# PV_MCU_IO.net
KiCad netlist of a schematic drawn in Altium Designer
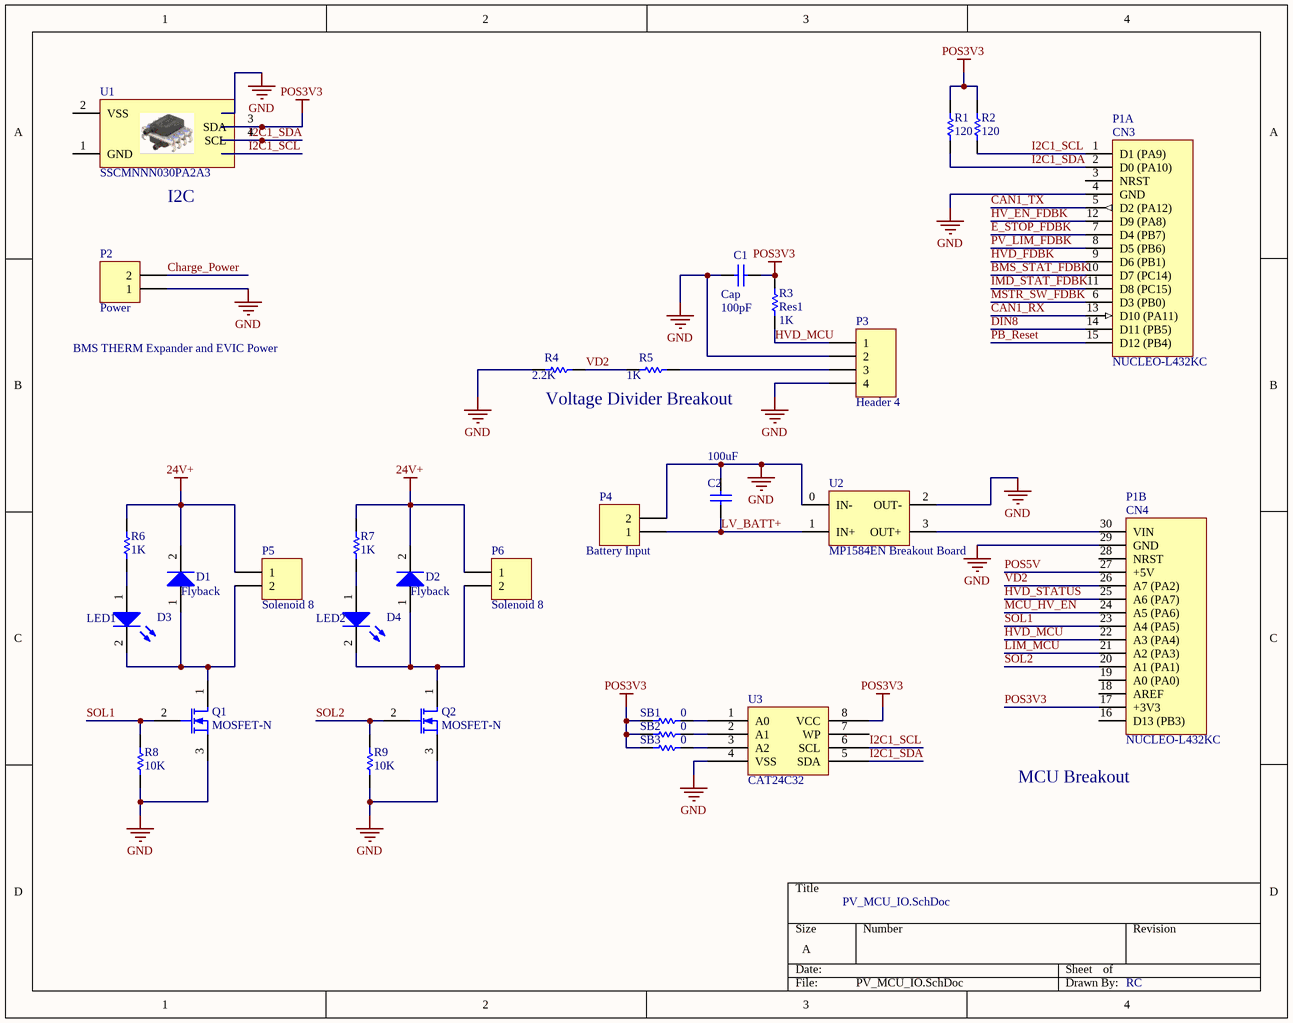
[diagram p0: PV_MCU_IO.SchDoc]

(export (version "E")
  (design (tool "Eeschema 10.0.6"))
  (components
    (comp (ref "C1")
      (value "Cap")
      (footprint "1206")
      (description "Capacitor")
      (fields (field (name "ALTIUM_VALUE") "100pF") (field (name "PUBLISHER") "Altium Limited"))
      (libsource (lib "Miscellaneous Devices") (part "Cap"))
    )
    (comp (ref "C2")
      (value "100uF")
      (footprint "CAPR5-4X5")
      (description "Capacitor")
      (fields (field (name "Comment") "Cap") (field (name "PUBLISHER") "Altium Limited"))
      (libsource (lib "Miscellaneous Devices") (part "Cap"))
    )
    (comp (ref "D1")
      (value "Flyback")
      (footprint "1N4007")
      (description "Default Diode")
      (fields (field (name "PUBLISHER") "Altium Limited"))
      (libsource (lib "Miscellaneous Devices") (part "Diode"))
    )
    (comp (ref "D2")
      (value "Flyback")
      (footprint "1N4007")
      (description "Default Diode")
      (fields (field (name "PUBLISHER") "Altium Limited"))
      (libsource (lib "Miscellaneous Devices") (part "Diode"))
    )
    (comp (ref "D3")
      (value "LED1")
      (footprint "1206 LED")
      (description "Typical RED, GREEN, YELLOW, AMBER GaAs LED")
      (fields (field (name "PUBLISHER") "Altium Limited"))
      (libsource (lib "Miscellaneous Devices") (part "LED2"))
    )
    (comp (ref "D4")
      (value "LED2")
      (footprint "1206 LED")
      (description "Typical RED, GREEN, YELLOW, AMBER GaAs LED")
      (fields (field (name "PUBLISHER") "Altium Limited"))
      (libsource (lib "Miscellaneous Devices") (part "LED2"))
    )
    (comp (ref "P1")
      (value "NUCLEO-L432KC")
      (footprint "NUCLEO-32")
      (description "STM32L432KC Development Board")
      (libsource (lib "ic") (part "NUCLEO-L432KC"))
    )
    (comp (ref "P2")
      (value "Power")
      (footprint "2POS TERM BLOCK")
      (description "Header, 2-Pin")
      (fields (field (name "PUBLISHER") "Altium Limited"))
      (libsource (lib "Miscellaneous Connectors") (part "Header 2"))
    )
    (comp (ref "P3")
      (value "Header 4")
      (footprint "4POS TERM BLOCK")
      (description "Header, 4-Pin")
      (fields (field (name "PUBLISHER") "Altium Limited"))
      (libsource (lib "Miscellaneous Connectors") (part "Header 4"))
    )
    (comp (ref "P4")
      (value "Battery Input")
      (footprint "2POS TERM BLOCK")
      (description "Header, 2-Pin")
      (fields (field (name "PUBLISHER") "Altium Limited"))
      (libsource (lib "Miscellaneous Connectors") (part "Header 2"))
    )
    (comp (ref "P5")
      (value "Solenoid 8")
      (footprint "2POS TERM BLOCK")
      (description "Header, 2-Pin")
      (fields (field (name "PUBLISHER") "Altium Limited"))
      (libsource (lib "") (part "Header 2_1"))
    )
    (comp (ref "P6")
      (value "Solenoid 8")
      (footprint "2POS TERM BLOCK")
      (description "Header, 2-Pin")
      (fields (field (name "PUBLISHER") "Altium Limited"))
      (libsource (lib "") (part "Header 2_1"))
    )
    (comp (ref "Q1")
      (value "MOSFET-N")
      (footprint "SOT-23-3")
      (description "N-Channel MOSFET")
      (fields (field (name "PUBLISHER") "Altium Limited"))
      (libsource (lib "Miscellaneous Devices") (part "MOSFET-N"))
    )
    (comp (ref "Q2")
      (value "MOSFET-N")
      (footprint "SOT-23-3")
      (description "N-Channel MOSFET")
      (fields (field (name "PUBLISHER") "Altium Limited"))
      (libsource (lib "Miscellaneous Devices") (part "MOSFET-N"))
    )
    (comp (ref "R1")
      (value "120")
      (footprint "1206")
      (description "Resistor")
      (fields (field (name "Comment") "Res1") (field (name "PUBLISHER") "Altium Limited"))
      (libsource (lib "Miscellaneous Devices") (part "Res1"))
    )
    (comp (ref "R2")
      (value "120")
      (footprint "1206")
      (description "Resistor")
      (fields (field (name "Comment") "Res1") (field (name "PUBLISHER") "Altium Limited"))
      (libsource (lib "Miscellaneous Devices") (part "Res1"))
    )
    (comp (ref "R3")
      (value "Res1")
      (footprint "1206")
      (description "Resistor")
      (fields (field (name "ALTIUM_VALUE") "1K") (field (name "PUBLISHER") "Altium Limited"))
      (libsource (lib "Miscellaneous Devices") (part "Res1"))
    )
    (comp (ref "R4")
      (value "2.2K")
      (footprint "1206")
      (description "Resistor")
      (fields (field (name "Comment") "Res1") (field (name "PUBLISHER") "Altium Limited"))
      (libsource (lib "Miscellaneous Devices") (part "Res1"))
    )
    (comp (ref "R5")
      (value "1K")
      (footprint "1206")
      (description "Resistor")
      (fields (field (name "Comment") "Res1") (field (name "PUBLISHER") "Altium Limited"))
      (libsource (lib "Miscellaneous Devices") (part "Res1"))
    )
    (comp (ref "R6")
      (value "1K")
      (footprint "1206")
      (description "Resistor")
      (fields (field (name "Comment") "Res1") (field (name "PUBLISHER") "Altium Limited"))
      (libsource (lib "Miscellaneous Devices") (part "Res1"))
    )
    (comp (ref "R7")
      (value "1K")
      (footprint "1206")
      (description "Resistor")
      (fields (field (name "Comment") "Res1") (field (name "PUBLISHER") "Altium Limited"))
      (libsource (lib "Miscellaneous Devices") (part "Res1"))
    )
    (comp (ref "R8")
      (value "10K")
      (footprint "1206")
      (description "Resistor")
      (fields (field (name "Comment") "Res1") (field (name "PUBLISHER") "Altium Limited"))
      (libsource (lib "Miscellaneous Devices") (part "Res1"))
    )
    (comp (ref "R9")
      (value "10K")
      (footprint "1206")
      (description "Resistor")
      (fields (field (name "Comment") "Res1") (field (name "PUBLISHER") "Altium Limited"))
      (libsource (lib "Miscellaneous Devices") (part "Res1"))
    )
    (comp (ref "SB1")
      (value "0")
      (footprint "6-0805_M")
      (description "Resistor")
      (fields (field (name "Comment") "Res1") (field (name "PUBLISHER") "Altium Limited"))
      (libsource (lib "Miscellaneous Devices") (part "Res1"))
    )
    (comp (ref "SB2")
      (value "0")
      (footprint "6-0805_M")
      (description "Resistor")
      (fields (field (name "Comment") "Res1") (field (name "PUBLISHER") "Altium Limited"))
      (libsource (lib "Miscellaneous Devices") (part "Res1"))
    )
    (comp (ref "SB3")
      (value "0")
      (footprint "6-0805_M")
      (description "Resistor")
      (fields (field (name "Comment") "Res1") (field (name "PUBLISHER") "Altium Limited"))
      (libsource (lib "Miscellaneous Devices") (part "Res1"))
    )
    (comp (ref "U1")
      (value "SSCMNNN030PA2A3")
      (footprint "8-SMT")
      (description "Honeywell Digital Pressure Sensor")
      (libsource (lib "ic") (part "SSCMNNN030PA2A3"))
    )
    (comp (ref "U2")
      (value "MP1584EN Breakout Board")
      (footprint "MP1584EN Breakout")
      (description "Buck Converter")
      (libsource (lib "ic") (part "MP1584EN Breakout Board"))
    )
    (comp (ref "U3")
      (value "CAT24C32")
      (footprint "SO8_N")
      (description "I2C EEPROM")
      (libsource (lib "ic") (part "CAT24C32"))
    )
  )
  (nets
    (net (code "1") (name "/BMS_STAT_FDBK") (class "Default")
      (node (ref "P1") (pin "10") (pinfunction "D7_(PC14)_10") (pintype "passive"))
    )
    (net (code "2") (name "/CAN1_RX") (class "Default")
      (node (ref "P1") (pin "13") (pinfunction "D10_(PA11)_13") (pintype "input"))
    )
    (net (code "3") (name "/CAN1_TX") (class "Default")
      (node (ref "P1") (pin "5") (pinfunction "D2_(PA12)_5") (pintype "output"))
    )
    (net (code "4") (name "/Charge_Power") (class "Default")
      (node (ref "P2") (pin "2") (pinfunction "2_2") (pintype "passive"))
    )
    (net (code "5") (name "/DIN8") (class "Default")
      (node (ref "P1") (pin "14") (pinfunction "D11_(PB5)_14") (pintype "passive"))
    )
    (net (code "6") (name "/E_STOP_FDBK") (class "Default")
      (node (ref "P1") (pin "7") (pinfunction "D4_(PB7)_7") (pintype "passive"))
    )
    (net (code "7") (name "/HVD_FDBK") (class "Default")
      (node (ref "P1") (pin "9") (pinfunction "D6_(PB1)_9") (pintype "passive"))
    )
    (net (code "8") (name "/HVD_MCU") (class "Default")
      (node (ref "P1") (pin "22") (pinfunction "A3_(PA4)_22") (pintype "passive"))
      (node (ref "P3") (pin "1") (pinfunction "1_1") (pintype "passive"))
      (node (ref "R3") (pin "1") (pinfunction "1_1") (pintype "passive"))
    )
    (net (code "9") (name "/HVD_STATUS") (class "Default")
      (node (ref "P1") (pin "25") (pinfunction "A6_(PA7)_25") (pintype "passive"))
    )
    (net (code "10") (name "/HV_EN_FDBK") (class "Default")
      (node (ref "P1") (pin "12") (pinfunction "D9_(PA8)_12") (pintype "passive"))
    )
    (net (code "11") (name "/I2C1_SCL") (class "Default")
      (node (ref "P1") (pin "1") (pinfunction "D1_(PA9)_1") (pintype "passive"))
      (node (ref "R2") (pin "1") (pinfunction "1_1") (pintype "passive"))
      (node (ref "U3") (pin "6") (pinfunction "SCL_6") (pintype "passive"))
    )
    (net (code "12") (name "/I2C1_SDA") (class "Default")
      (node (ref "P1") (pin "2") (pinfunction "D0_(PA10)_2") (pintype "passive"))
      (node (ref "R1") (pin "1") (pinfunction "1_1") (pintype "passive"))
      (node (ref "U1") (pin "4") (pinfunction "SCL_4") (pintype "passive"))
      (node (ref "U3") (pin "5") (pinfunction "SDA_5") (pintype "passive"))
    )
    (net (code "13") (name "/IMD_STAT_FDBK") (class "Default")
      (node (ref "P1") (pin "11") (pinfunction "D8_(PC15)_11") (pintype "passive"))
    )
    (net (code "14") (name "/LIM_MCU") (class "Default")
      (node (ref "P1") (pin "21") (pinfunction "A2_(PA3)_21") (pintype "passive"))
    )
    (net (code "15") (name "/LV_BATT+") (class "Default")
      (node (ref "C2") (pin "1") (pinfunction "1_1") (pintype "passive"))
      (node (ref "P4") (pin "1") (pinfunction "1_1") (pintype "passive"))
      (node (ref "U2") (pin "1") (pinfunction "IN+_1") (pintype "power_in"))
    )
    (net (code "16") (name "/MCU_HV_EN") (class "Default")
      (node (ref "P1") (pin "24") (pinfunction "A5_(PA6)_24") (pintype "passive"))
    )
    (net (code "17") (name "/MSTR_SW_FDBK") (class "Default")
      (node (ref "P1") (pin "6") (pinfunction "D3_(PB0)_6") (pintype "passive"))
    )
    (net (code "18") (name "/PB_Reset") (class "Default")
      (node (ref "P1") (pin "15") (pinfunction "D12_(PB4)_15") (pintype "passive"))
    )
    (net (code "19") (name "/POS5V") (class "Default")
      (node (ref "P1") (pin "27") (pinfunction "+5V_27") (pintype "passive"))
    )
    (net (code "20") (name "/PV_LIM_FDBK") (class "Default")
      (node (ref "P1") (pin "8") (pinfunction "D5_(PB6)_8") (pintype "passive"))
    )
    (net (code "21") (name "/SOL1") (class "Default")
      (node (ref "P1") (pin "23") (pinfunction "A4_(PA5)_23") (pintype "passive"))
      (node (ref "Q1") (pin "2") (pinfunction "G_2") (pintype "passive"))
      (node (ref "R8") (pin "2") (pinfunction "2_2") (pintype "passive"))
    )
    (net (code "22") (name "/SOL2") (class "Default")
      (node (ref "P1") (pin "20") (pinfunction "A1_(PA1)_20") (pintype "passive"))
      (node (ref "Q2") (pin "2") (pinfunction "G_2") (pintype "passive"))
      (node (ref "R9") (pin "2") (pinfunction "2_2") (pintype "passive"))
    )
    (net (code "23") (name "/VD2") (class "Default")
      (node (ref "P1") (pin "26") (pinfunction "A7_(PA2)_26") (pintype "passive"))
      (node (ref "R4") (pin "2") (pinfunction "2_2") (pintype "passive"))
      (node (ref "R5") (pin "1") (pinfunction "1_1") (pintype "passive"))
    )
    (net (code "24") (name "24V+") (class "Default")
      (node (ref "D1") (pin "2") (pinfunction "K_2") (pintype "passive"))
      (node (ref "D2") (pin "2") (pinfunction "K_2") (pintype "passive"))
      (node (ref "P5") (pin "1") (pinfunction "1_1") (pintype "passive"))
      (node (ref "P6") (pin "1") (pinfunction "1_1") (pintype "passive"))
      (node (ref "R6") (pin "2") (pinfunction "2_2") (pintype "passive"))
      (node (ref "R7") (pin "2") (pinfunction "2_2") (pintype "passive"))
    )
    (net (code "25") (name "GND") (class "Default")
      (node (ref "C1") (pin "2") (pinfunction "2_2") (pintype "passive"))
      (node (ref "C2") (pin "2") (pinfunction "2_2") (pintype "passive"))
      (node (ref "P1") (pin "29") (pinfunction "GND_29") (pintype "passive"))
      (node (ref "P1") (pin "4") (pinfunction "GND_4") (pintype "passive"))
      (node (ref "P2") (pin "1") (pinfunction "1_1") (pintype "passive"))
      (node (ref "P3") (pin "2") (pinfunction "2_2") (pintype "passive"))
      (node (ref "P3") (pin "4") (pinfunction "4_4") (pintype "passive"))
      (node (ref "P4") (pin "2") (pinfunction "2_2") (pintype "passive"))
      (node (ref "Q1") (pin "3") (pinfunction "S_3") (pintype "passive"))
      (node (ref "Q2") (pin "3") (pinfunction "S_3") (pintype "passive"))
      (node (ref "R4") (pin "1") (pinfunction "1_1") (pintype "passive"))
      (node (ref "R8") (pin "1") (pinfunction "1_1") (pintype "passive"))
      (node (ref "R9") (pin "1") (pinfunction "1_1") (pintype "passive"))
      (node (ref "U2") (pin "0") (pinfunction "IN-_0") (pintype "passive"))
      (node (ref "U2") (pin "2") (pinfunction "OUT-_2") (pintype "passive"))
      (node (ref "U3") (pin "4") (pinfunction "VSS_4") (pintype "passive"))
    )
    (net (code "26") (name "Net-(D1-A)") (class "Default")
      (node (ref "D1") (pin "1") (pinfunction "A_1") (pintype "passive"))
      (node (ref "D3") (pin "2") (pinfunction "K_2") (pintype "passive"))
      (node (ref "P5") (pin "2") (pinfunction "2_2") (pintype "passive"))
      (node (ref "Q1") (pin "1") (pinfunction "D_1") (pintype "passive"))
    )
    (net (code "27") (name "Net-(D2-A)") (class "Default")
      (node (ref "D2") (pin "1") (pinfunction "A_1") (pintype "passive"))
      (node (ref "D4") (pin "2") (pinfunction "K_2") (pintype "passive"))
      (node (ref "P6") (pin "2") (pinfunction "2_2") (pintype "passive"))
      (node (ref "Q2") (pin "1") (pinfunction "D_1") (pintype "passive"))
    )
    (net (code "28") (name "Net-(D3-A)") (class "Default")
      (node (ref "D3") (pin "1") (pinfunction "A_1") (pintype "passive"))
      (node (ref "R6") (pin "1") (pinfunction "1_1") (pintype "passive"))
    )
    (net (code "29") (name "Net-(D4-A)") (class "Default")
      (node (ref "D4") (pin "1") (pinfunction "A_1") (pintype "passive"))
      (node (ref "R7") (pin "1") (pinfunction "1_1") (pintype "passive"))
    )
    (net (code "30") (name "Net-(P1B-VIN)") (class "Default")
      (node (ref "P1") (pin "30") (pinfunction "VIN_30") (pintype "passive"))
      (node (ref "U2") (pin "3") (pinfunction "OUT+_3") (pintype "power_in"))
    )
    (net (code "31") (name "Net-(P3-Pad3)") (class "Default")
      (node (ref "P3") (pin "3") (pinfunction "3_3") (pintype "passive"))
      (node (ref "R5") (pin "2") (pinfunction "2_2") (pintype "passive"))
    )
    (net (code "32") (name "Net-(U3-A0)") (class "Default")
      (node (ref "SB1") (pin "1") (pinfunction "1_1") (pintype "passive"))
      (node (ref "U3") (pin "1") (pinfunction "A0_1") (pintype "passive"))
    )
    (net (code "33") (name "Net-(U3-A1)") (class "Default")
      (node (ref "SB2") (pin "1") (pinfunction "1_1") (pintype "passive"))
      (node (ref "U3") (pin "2") (pinfunction "A1_2") (pintype "passive"))
    )
    (net (code "34") (name "Net-(U3-A2)") (class "Default")
      (node (ref "SB3") (pin "1") (pinfunction "1_1") (pintype "passive"))
      (node (ref "U3") (pin "3") (pinfunction "A2_3") (pintype "passive"))
    )
    (net (code "35") (name "POS3V3") (class "Default")
      (node (ref "C1") (pin "1") (pinfunction "1_1") (pintype "passive"))
      (node (ref "P1") (pin "17") (pinfunction "+3V3_17") (pintype "passive"))
      (node (ref "R1") (pin "2") (pinfunction "2_2") (pintype "passive"))
      (node (ref "R2") (pin "2") (pinfunction "2_2") (pintype "passive"))
      (node (ref "R3") (pin "2") (pinfunction "2_2") (pintype "passive"))
      (node (ref "SB1") (pin "2") (pinfunction "2_2") (pintype "passive"))
      (node (ref "SB2") (pin "2") (pinfunction "2_2") (pintype "passive"))
      (node (ref "SB3") (pin "2") (pinfunction "2_2") (pintype "passive"))
      (node (ref "U1") (pin "3") (pinfunction "SDA_3") (pintype "passive"))
      (node (ref "U3") (pin "8") (pinfunction "VCC_8") (pintype "power_in"))
    )
    (net (code "36") (name "unconnected-(P1A-NRST-Pad3)") (class "Default")
      (node (ref "P1") (pin "3") (pinfunction "NRST_3") (pintype "passive"))
    )
    (net (code "37") (name "unconnected-(P1B-A0_(PA0)-Pad19)") (class "Default")
      (node (ref "P1") (pin "19") (pinfunction "A0_(PA0)_19") (pintype "passive"))
    )
    (net (code "38") (name "unconnected-(P1B-AREF-Pad18)") (class "Default")
      (node (ref "P1") (pin "18") (pinfunction "AREF_18") (pintype "passive"))
    )
    (net (code "39") (name "unconnected-(P1B-D13_(PB3)-Pad16)") (class "Default")
      (node (ref "P1") (pin "16") (pinfunction "D13_(PB3)_16") (pintype "passive"))
    )
    (net (code "40") (name "unconnected-(P1B-NRST-Pad28)") (class "Default")
      (node (ref "P1") (pin "28") (pinfunction "NRST_28") (pintype "passive"))
    )
    (net (code "41") (name "unconnected-(U1-GND-Pad1)") (class "Default")
      (node (ref "U1") (pin "1") (pinfunction "GND_1") (pintype "power_in"))
    )
    (net (code "42") (name "unconnected-(U1-VSS-Pad2)") (class "Default")
      (node (ref "U1") (pin "2") (pinfunction "VSS_2") (pintype "power_in"))
    )
    (net (code "43") (name "unconnected-(U3-WP-Pad7)") (class "Default")
      (node (ref "U3") (pin "7") (pinfunction "WP_7") (pintype "passive"))
    )
  )
)
